# Remote1.net
KiCad netlist of a schematic drawn in EAGLE
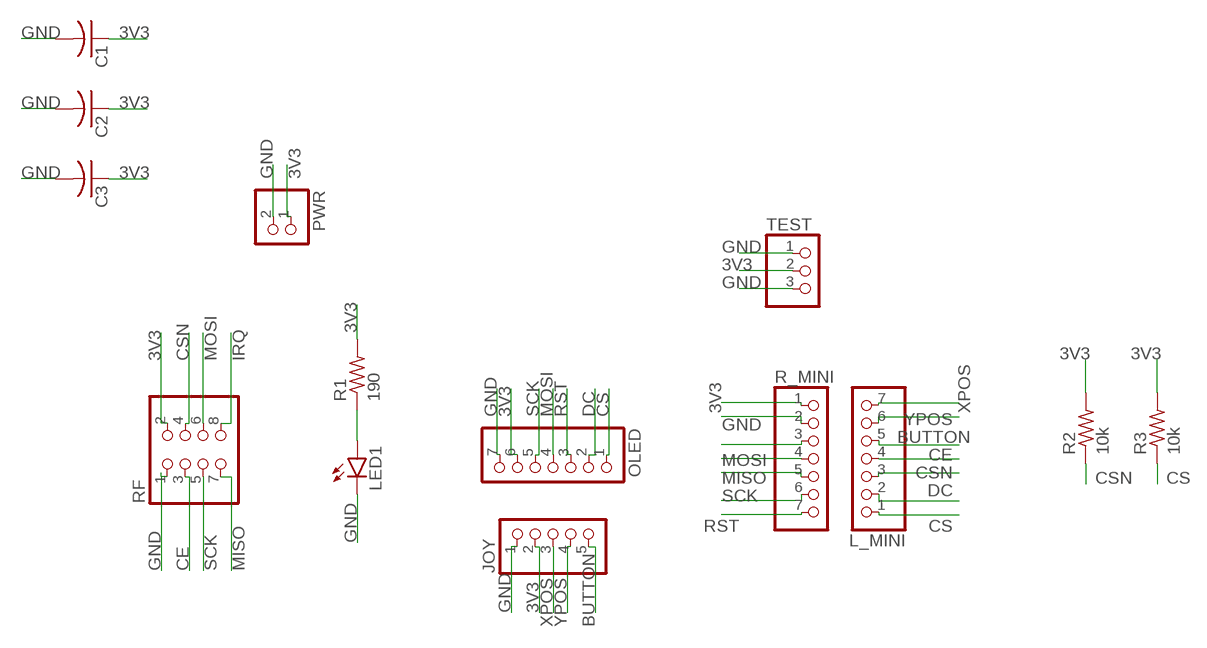
[diagram p0: schematic, sheet 1]

(export (version "E")
  (design (tool "Eeschema 10.0.6"))
  (components
    (comp (ref "C1")
      (value "C-US025-024X044")
      (footprint "eagle-import:C025-024X044")
      (libsource (lib "eagle-import") (part "C-US025-024X044"))
    )
    (comp (ref "C2")
      (value "C-US025-024X044")
      (footprint "eagle-import:C025-024X044")
      (libsource (lib "eagle-import") (part "C-US025-024X044"))
    )
    (comp (ref "C3")
      (value "C-US025-024X044")
      (footprint "eagle-import:C025-024X044")
      (libsource (lib "eagle-import") (part "C-US025-024X044"))
    )
    (comp (ref "JOY")
      (value "PINHD-1X5/90")
      (footprint "eagle-import:1X05_90")
      (libsource (lib "eagle-import") (part "PINHD-1X5/90"))
    )
    (comp (ref "LED1")
      (value "LED5MM")
      (footprint "eagle-import:LED5MM")
      (libsource (lib "eagle-import") (part "LED5MM"))
    )
    (comp (ref "L_MINI")
      (value "PINHD-1X7")
      (footprint "eagle-import:1X07")
      (libsource (lib "eagle-import") (part "PINHD-1X7"))
    )
    (comp (ref "OLED")
      (value "PINHD-1X7")
      (footprint "eagle-import:1X07")
      (libsource (lib "eagle-import") (part "PINHD-1X7"))
    )
    (comp (ref "PWR")
      (value "PINHD-1X2")
      (footprint "eagle-import:1X02")
      (libsource (lib "eagle-import") (part "PINHD-1X2"))
    )
    (comp (ref "R1")
      (value "190")
      (footprint "eagle-import:0204_7")
      (libsource (lib "eagle-import") (part "R-US_0204/7"))
    )
    (comp (ref "R2")
      (value "10k")
      (footprint "eagle-import:0204_7")
      (libsource (lib "eagle-import") (part "R-US_0204/7"))
    )
    (comp (ref "R3")
      (value "10k")
      (footprint "eagle-import:0204_7")
      (libsource (lib "eagle-import") (part "R-US_0204/7"))
    )
    (comp (ref "RF")
      (value "PINHD-2X4")
      (footprint "eagle-import:2X04")
      (libsource (lib "eagle-import") (part "PINHD-2X4"))
    )
    (comp (ref "R_MINI")
      (value "PINHD-1X7")
      (footprint "eagle-import:1X07")
      (libsource (lib "eagle-import") (part "PINHD-1X7"))
    )
    (comp (ref "TEST")
      (value "PINHD-1X3")
      (footprint "eagle-import:1X03")
      (libsource (lib "eagle-import") (part "PINHD-1X3"))
    )
  )
  (nets
    (net (code "1") (name "/3V3") (class "Default")
      (node (ref "C1") (pin "1") (pinfunction "1_1") (pintype "passive"))
      (node (ref "C2") (pin "1") (pinfunction "1_1") (pintype "passive"))
      (node (ref "C3") (pin "1") (pinfunction "1_1") (pintype "passive"))
      (node (ref "JOY") (pin "2") (pinfunction "2_2") (pintype "passive"))
      (node (ref "OLED") (pin "6") (pinfunction "6_6") (pintype "passive"))
      (node (ref "PWR") (pin "1") (pinfunction "1_1") (pintype "passive"))
      (node (ref "R1") (pin "2") (pinfunction "2_2") (pintype "passive"))
      (node (ref "R2") (pin "2") (pinfunction "2_2") (pintype "passive"))
      (node (ref "R3") (pin "2") (pinfunction "2_2") (pintype "passive"))
      (node (ref "RF") (pin "2") (pinfunction "2_2") (pintype "passive"))
      (node (ref "R_MINI") (pin "1") (pinfunction "1_1") (pintype "passive"))
      (node (ref "TEST") (pin "2") (pinfunction "2_2") (pintype "passive"))
    )
    (net (code "2") (name "/BUTTON") (class "Default")
      (node (ref "JOY") (pin "5") (pinfunction "5_5") (pintype "passive"))
      (node (ref "L_MINI") (pin "5") (pinfunction "5_5") (pintype "passive"))
    )
    (net (code "3") (name "/CE") (class "Default")
      (node (ref "L_MINI") (pin "4") (pinfunction "4_4") (pintype "passive"))
      (node (ref "RF") (pin "3") (pinfunction "3_3") (pintype "passive"))
    )
    (net (code "4") (name "/CS") (class "Default")
      (node (ref "L_MINI") (pin "1") (pinfunction "1_1") (pintype "passive"))
      (node (ref "OLED") (pin "1") (pinfunction "1_1") (pintype "passive"))
      (node (ref "R3") (pin "1") (pinfunction "1_1") (pintype "passive"))
    )
    (net (code "5") (name "/CSN") (class "Default")
      (node (ref "L_MINI") (pin "3") (pinfunction "3_3") (pintype "passive"))
      (node (ref "R2") (pin "1") (pinfunction "1_1") (pintype "passive"))
      (node (ref "RF") (pin "4") (pinfunction "4_4") (pintype "passive"))
    )
    (net (code "6") (name "/DC") (class "Default")
      (node (ref "L_MINI") (pin "2") (pinfunction "2_2") (pintype "passive"))
      (node (ref "OLED") (pin "2") (pinfunction "2_2") (pintype "passive"))
    )
    (net (code "7") (name "/GND") (class "Default")
      (node (ref "C1") (pin "2") (pinfunction "2_2") (pintype "passive"))
      (node (ref "C2") (pin "2") (pinfunction "2_2") (pintype "passive"))
      (node (ref "C3") (pin "2") (pinfunction "2_2") (pintype "passive"))
      (node (ref "JOY") (pin "1") (pinfunction "1_1") (pintype "passive"))
      (node (ref "LED1") (pin "K") (pinfunction "C_K") (pintype "passive"))
      (node (ref "OLED") (pin "7") (pinfunction "7_7") (pintype "passive"))
      (node (ref "PWR") (pin "2") (pinfunction "2_2") (pintype "passive"))
      (node (ref "RF") (pin "1") (pinfunction "1_1") (pintype "passive"))
      (node (ref "R_MINI") (pin "2") (pinfunction "2_2") (pintype "passive"))
      (node (ref "TEST") (pin "1") (pinfunction "1_1") (pintype "passive"))
      (node (ref "TEST") (pin "3") (pinfunction "3_3") (pintype "passive"))
    )
    (net (code "8") (name "/IRQ") (class "Default")
      (node (ref "RF") (pin "8") (pinfunction "8_8") (pintype "passive"))
    )
    (net (code "9") (name "/MISO") (class "Default")
      (node (ref "RF") (pin "7") (pinfunction "7_7") (pintype "passive"))
      (node (ref "R_MINI") (pin "5") (pinfunction "5_5") (pintype "passive"))
    )
    (net (code "10") (name "/MOSI") (class "Default")
      (node (ref "OLED") (pin "4") (pinfunction "4_4") (pintype "passive"))
      (node (ref "RF") (pin "6") (pinfunction "6_6") (pintype "passive"))
      (node (ref "R_MINI") (pin "4") (pinfunction "4_4") (pintype "passive"))
    )
    (net (code "11") (name "/RST") (class "Default")
      (node (ref "OLED") (pin "3") (pinfunction "3_3") (pintype "passive"))
      (node (ref "R_MINI") (pin "7") (pinfunction "7_7") (pintype "passive"))
    )
    (net (code "12") (name "/SCK") (class "Default")
      (node (ref "OLED") (pin "5") (pinfunction "5_5") (pintype "passive"))
      (node (ref "RF") (pin "5") (pinfunction "5_5") (pintype "passive"))
      (node (ref "R_MINI") (pin "6") (pinfunction "6_6") (pintype "passive"))
    )
    (net (code "13") (name "/XPOS") (class "Default")
      (node (ref "JOY") (pin "3") (pinfunction "3_3") (pintype "passive"))
      (node (ref "L_MINI") (pin "7") (pinfunction "7_7") (pintype "passive"))
    )
    (net (code "14") (name "/YPOS") (class "Default")
      (node (ref "JOY") (pin "4") (pinfunction "4_4") (pintype "passive"))
      (node (ref "L_MINI") (pin "6") (pinfunction "6_6") (pintype "passive"))
    )
    (net (code "15") (name "Net-(LED1-PadA)") (class "Default")
      (node (ref "LED1") (pin "A") (pinfunction "A_A") (pintype "passive"))
      (node (ref "R1") (pin "1") (pinfunction "1_1") (pintype "passive"))
    )
    (net (code "16") (name "unconnected-(R_MINI-Pad3)") (class "Default")
      (node (ref "R_MINI") (pin "3") (pinfunction "3_3") (pintype "passive"))
    )
  )
)
